# Jumpers_High_Low.net
KiCad netlist of a schematic drawn in Altium Designer
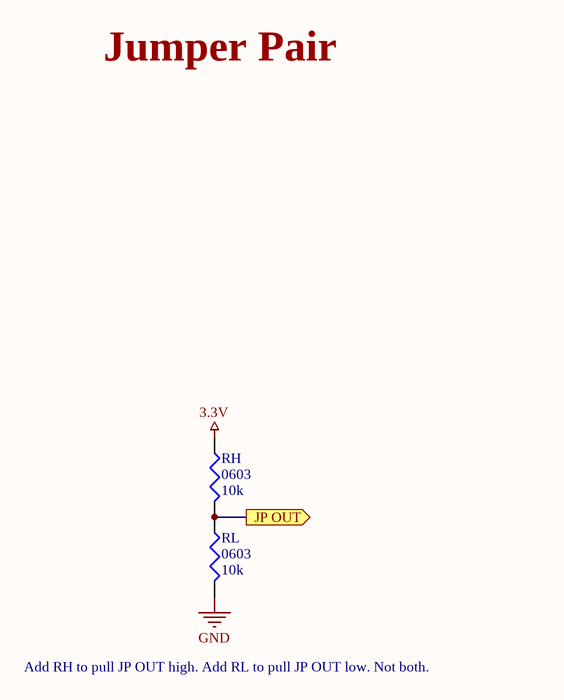
[diagram p0: Jumpers High Low.SchDoc]

(export (version "E")
  (design (tool "Eeschema 10.0.6"))
  (components
    (comp (ref "RH")
      (value "0603")
      (footprint "J1-0603")
      (description "Resistor")
      (fields (field (name "ALTIUM_VALUE") "10k") (field (name "PUBLISHER") "Altium Limited"))
      (libsource (lib "Miscellaneous Devices") (part "Res3"))
    )
    (comp (ref "RL")
      (value "0603")
      (footprint "J1-0603")
      (description "Resistor")
      (fields (field (name "ALTIUM_VALUE") "10k") (field (name "PUBLISHER") "Altium Limited"))
      (libsource (lib "Miscellaneous Devices") (part "Res3"))
    )
  )
  (nets
    (net (code "1") (name "/JP OUT") (class "Default")
      (node (ref "RH") (pin "2") (pinfunction "2_2") (pintype "passive"))
      (node (ref "RL") (pin "1") (pinfunction "1_1") (pintype "passive"))
    )
    (net (code "2") (name "3.3V") (class "Default")
      (node (ref "RH") (pin "1") (pinfunction "1_1") (pintype "passive"))
    )
    (net (code "3") (name "GND") (class "Default")
      (node (ref "RL") (pin "2") (pinfunction "2_2") (pintype "passive"))
    )
  )
)
